# Schematic.net
KiCad netlist of a schematic drawn in Altium Designer
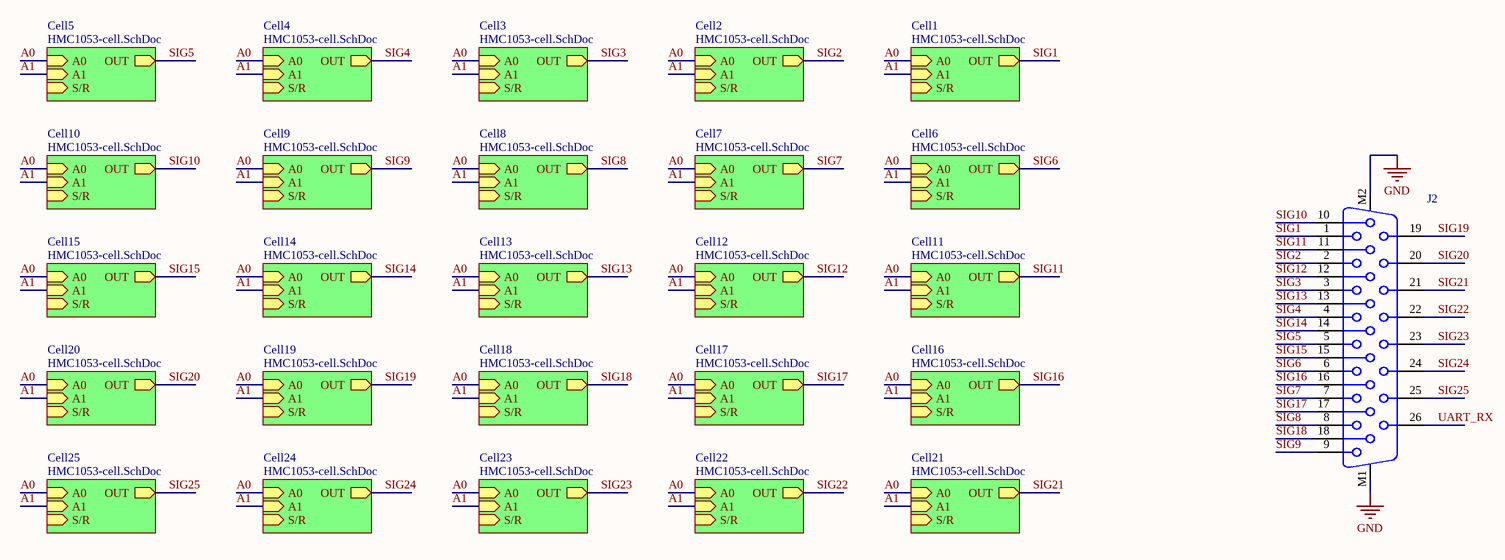
[diagram p0: Schematic.SchDoc]

(export (version "E")
  (design (tool "Eeschema 10.0.6"))
  (components
    (comp (ref "J2")
      (value "D-sub_26")
      (footprint "D-sub_26")
      (description "Female High Density PCB Connector with Hex Screw WR-DSUB, Angled, 26 pins")
      (fields
        (field (name "MANUFACTURER") "Wurth Elektronik")
        (field (name "PART NUMBER") "618026330923")
        (field (name "PUBLISHER") "WurthElektronik")
      )
      (libsource (lib "symbols") (part "D-sub_26"))
    )
  )
  (nets
    (net (code "3") (name "/SIG1") (class "Default")
      (node (ref "J2") (pin "1") (pinfunction "1_1") (pintype "passive"))
    )
    (net (code "4") (name "/SIG2") (class "Default")
      (node (ref "J2") (pin "2") (pinfunction "2_2") (pintype "passive"))
    )
    (net (code "5") (name "/SIG3") (class "Default")
      (node (ref "J2") (pin "3") (pinfunction "3_3") (pintype "passive"))
    )
    (net (code "6") (name "/SIG4") (class "Default")
      (node (ref "J2") (pin "4") (pinfunction "4_4") (pintype "passive"))
    )
    (net (code "7") (name "/SIG5") (class "Default")
      (node (ref "J2") (pin "5") (pinfunction "5_5") (pintype "passive"))
    )
    (net (code "8") (name "/SIG6") (class "Default")
      (node (ref "J2") (pin "6") (pinfunction "6_6") (pintype "passive"))
    )
    (net (code "9") (name "/SIG7") (class "Default")
      (node (ref "J2") (pin "7") (pinfunction "7_7") (pintype "passive"))
    )
    (net (code "10") (name "/SIG8") (class "Default")
      (node (ref "J2") (pin "8") (pinfunction "8_8") (pintype "passive"))
    )
    (net (code "11") (name "/SIG9") (class "Default")
      (node (ref "J2") (pin "9") (pinfunction "9_9") (pintype "passive"))
    )
    (net (code "12") (name "/SIG10") (class "Default")
      (node (ref "J2") (pin "10") (pinfunction "10_10") (pintype "passive"))
    )
    (net (code "13") (name "/SIG11") (class "Default")
      (node (ref "J2") (pin "11") (pinfunction "11_11") (pintype "passive"))
    )
    (net (code "14") (name "/SIG12") (class "Default")
      (node (ref "J2") (pin "12") (pinfunction "12_12") (pintype "passive"))
    )
    (net (code "15") (name "/SIG13") (class "Default")
      (node (ref "J2") (pin "13") (pinfunction "13_13") (pintype "passive"))
    )
    (net (code "16") (name "/SIG14") (class "Default")
      (node (ref "J2") (pin "14") (pinfunction "14_14") (pintype "passive"))
    )
    (net (code "17") (name "/SIG15") (class "Default")
      (node (ref "J2") (pin "15") (pinfunction "15_15") (pintype "passive"))
    )
    (net (code "18") (name "/SIG16") (class "Default")
      (node (ref "J2") (pin "16") (pinfunction "16_16") (pintype "passive"))
    )
    (net (code "19") (name "/SIG17") (class "Default")
      (node (ref "J2") (pin "17") (pinfunction "17_17") (pintype "passive"))
    )
    (net (code "20") (name "/SIG18") (class "Default")
      (node (ref "J2") (pin "18") (pinfunction "18_18") (pintype "passive"))
    )
    (net (code "21") (name "/SIG19") (class "Default")
      (node (ref "J2") (pin "19") (pinfunction "19_19") (pintype "passive"))
    )
    (net (code "22") (name "/SIG20") (class "Default")
      (node (ref "J2") (pin "20") (pinfunction "20_20") (pintype "passive"))
    )
    (net (code "23") (name "/SIG21") (class "Default")
      (node (ref "J2") (pin "21") (pinfunction "21_21") (pintype "passive"))
    )
    (net (code "24") (name "/SIG22") (class "Default")
      (node (ref "J2") (pin "22") (pinfunction "22_22") (pintype "passive"))
    )
    (net (code "25") (name "/SIG23") (class "Default")
      (node (ref "J2") (pin "23") (pinfunction "23_23") (pintype "passive"))
    )
    (net (code "26") (name "/SIG24") (class "Default")
      (node (ref "J2") (pin "24") (pinfunction "24_24") (pintype "passive"))
    )
    (net (code "27") (name "/SIG25") (class "Default")
      (node (ref "J2") (pin "25") (pinfunction "25_25") (pintype "passive"))
    )
    (net (code "53") (name "/UART_RX") (class "Default")
      (node (ref "J2") (pin "26") (pinfunction "26_26") (pintype "passive"))
    )
    (net (code "54") (name "GND") (class "Default")
      (node (ref "J2") (pin "M1") (pinfunction "M1_M1") (pintype "passive"))
      (node (ref "J2") (pin "M2") (pinfunction "M2_M2") (pintype "passive"))
    )
  )
)
